# STM_mcu.net
KiCad netlist of a schematic drawn in Altium Designer
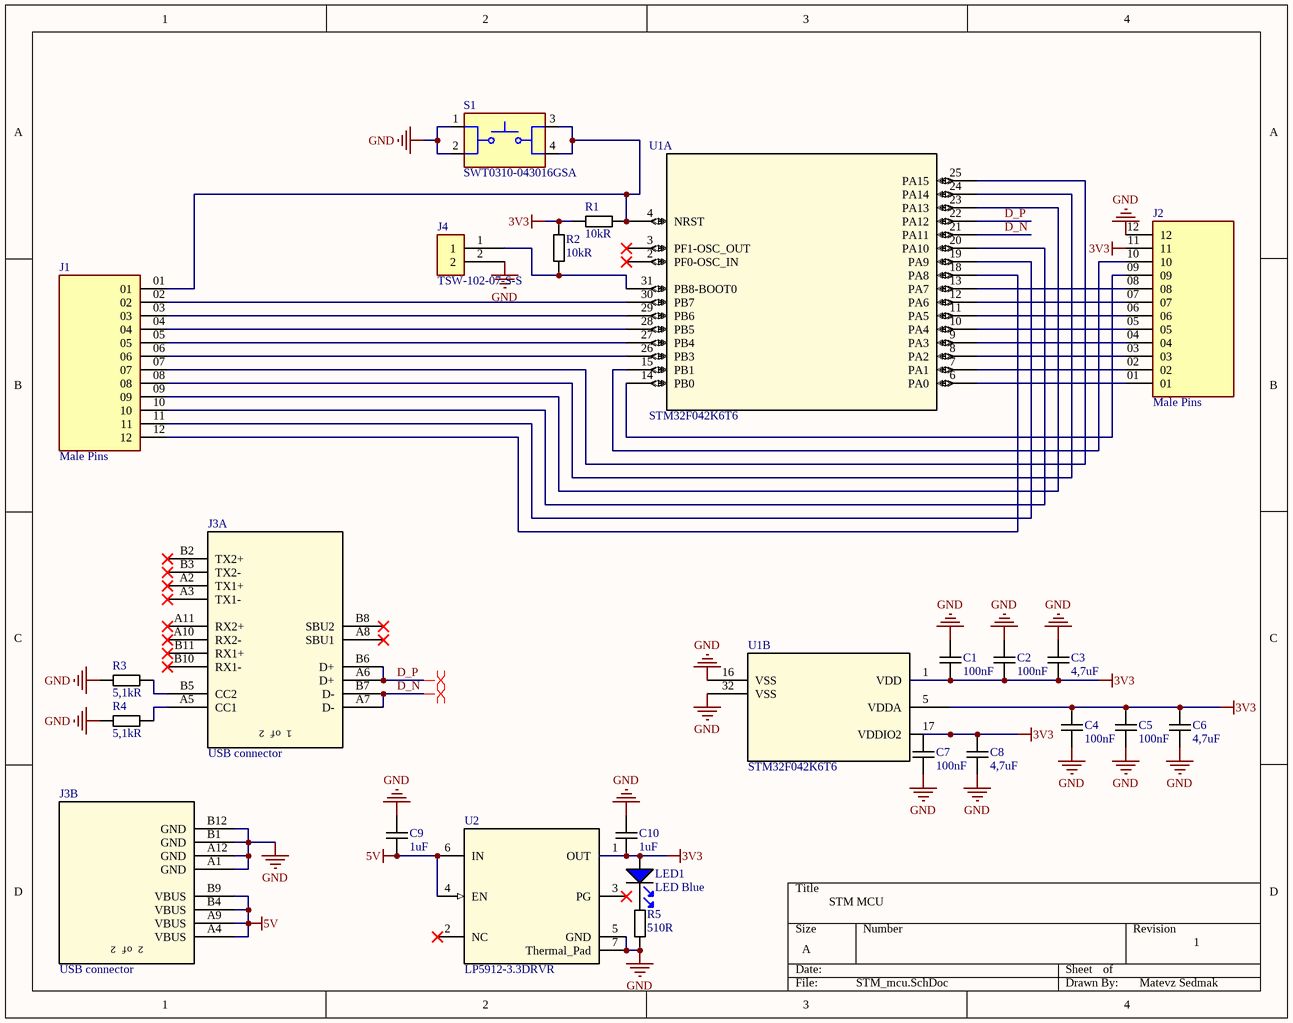
[diagram p0: STM_mcu.SchDoc]

(export (version "E")
  (design (tool "Eeschema 10.0.6"))
  (components
    (comp (ref "C1")
      (value "100nF")
      (footprint "CAPACITOR_0402")
      (description "0.1 µF ±20% 50V Ceramic Capacitor X5R 0402 (1005 Metric)")
      (fields (field (name "PART NUMBER") "CGA2B3X5R1H104M050BB"))
      (libsource (lib "STM_mcu") (part "100nF-50V-0402"))
    )
    (comp (ref "C2")
      (value "100nF")
      (footprint "CAPACITOR_0402")
      (description "0.1 µF ±20% 50V Ceramic Capacitor X5R 0402 (1005 Metric)")
      (fields (field (name "PART NUMBER") "CGA2B3X5R1H104M050BB"))
      (libsource (lib "STM_mcu") (part "100nF-50V-0402"))
    )
    (comp (ref "C3")
      (value "4,7uF")
      (footprint "CAPACITOR_0603")
      (description "4.7 µF ±10% 25V Ceramic Capacitor X5R 0603 (1608 Metric)")
      (fields (field (name "PART NUMBER") "C1608X5R1E475K080AC"))
      (libsource (lib "STM_mcu") (part "4,7uF-25V-0603"))
    )
    (comp (ref "C4")
      (value "100nF")
      (footprint "CAPACITOR_0402")
      (description "0.1 µF ±20% 50V Ceramic Capacitor X5R 0402 (1005 Metric)")
      (fields (field (name "PART NUMBER") "CGA2B3X5R1H104M050BB"))
      (libsource (lib "STM_mcu") (part "100nF-50V-0402"))
    )
    (comp (ref "C5")
      (value "100nF")
      (footprint "CAPACITOR_0402")
      (description "0.1 µF ±20% 50V Ceramic Capacitor X5R 0402 (1005 Metric)")
      (fields (field (name "PART NUMBER") "CGA2B3X5R1H104M050BB"))
      (libsource (lib "STM_mcu") (part "100nF-50V-0402"))
    )
    (comp (ref "C6")
      (value "4,7uF")
      (footprint "CAPACITOR_0603")
      (description "4.7 µF ±10% 25V Ceramic Capacitor X5R 0603 (1608 Metric)")
      (fields (field (name "PART NUMBER") "C1608X5R1E475K080AC"))
      (libsource (lib "STM_mcu") (part "4,7uF-25V-0603"))
    )
    (comp (ref "C7")
      (value "100nF")
      (footprint "CAPACITOR_0402")
      (description "0.1 µF ±20% 50V Ceramic Capacitor X5R 0402 (1005 Metric)")
      (fields (field (name "PART NUMBER") "CGA2B3X5R1H104M050BB"))
      (libsource (lib "STM_mcu") (part "100nF-50V-0402"))
    )
    (comp (ref "C8")
      (value "4,7uF")
      (footprint "CAPACITOR_0603")
      (description "4.7 µF ±10% 25V Ceramic Capacitor X5R 0603 (1608 Metric)")
      (fields (field (name "PART NUMBER") "C1608X5R1E475K080AC"))
      (libsource (lib "STM_mcu") (part "4,7uF-25V-0603"))
    )
    (comp (ref "C9")
      (value "1uF")
      (footprint "CAPACITOR_0603")
      (description "1 µF ±10% 25V Ceramic Capacitor X7R 0603 (1608 Metric)")
      (fields (field (name "PART NUMBER") "CGA3E1X7R1E105K080AC"))
      (libsource (lib "STM_mcu") (part "1uF-25V-0603"))
    )
    (comp (ref "C10")
      (value "1uF")
      (footprint "CAPACITOR_0603")
      (description "1 µF ±10% 25V Ceramic Capacitor X7R 0603 (1608 Metric)")
      (fields (field (name "PART NUMBER") "CGA3E1X7R1E105K080AC"))
      (libsource (lib "STM_mcu") (part "1uF-25V-0603"))
    )
    (comp (ref "J1")
      (value "Male Pins")
      (footprint "SAMTEC_TSW-112-07-L-S")
      (description "Connector Header Through Hole 12 position 0.100\" (2.54mm)")
      (fields (field (name "PART NUMBER") "TSW-112-07-L-S"))
      (libsource (lib "") (part "TSW-112-07-L-S_1"))
    )
    (comp (ref "J2")
      (value "Male Pins")
      (footprint "SAMTEC_TSW-112-07-L-S")
      (description "Connector Header Through Hole 12 position 0.100\" (2.54mm)")
      (fields (field (name "PART NUMBER") "TSW-112-07-L-S"))
      (libsource (lib "STM_mcu") (part "TSW-112-07-L-S"))
    )
    (comp (ref "J3")
      (value "USB connector")
      (footprint "USB_C_CONN_1054500101")
      (fields (field (name "PART NUMBER") "1054500101"))
      (libsource (lib "STM_mcu") (part "USB_1054500101"))
    )
    (comp (ref "J4")
      (value "TSW-102-07-S-S")
      (footprint "SAMTEC_TSW-102-07-L-S")
      (description "Connector Header Through Hole 2 position 0.100\" (2.54mm)")
      (libsource (lib "STM_mcu") (part "TSW-102-07-S-S"))
    )
    (comp (ref "LED1")
      (value "LED Blue")
      (footprint "LED_0603")
      (description "Blue 470nm LED Indication - Discrete 3.2V 0603 (1608 Metric)")
      (fields (field (name "PART NUMBER") "150060BS75000"))
      (libsource (lib "STM_mcu") (part "LED-Blue-0603"))
    )
    (comp (ref "R1")
      (value "10kR")
      (footprint "RESISTOR_0402")
      (description "10 kOhms ±1% 0.063W, 1/16W Chip Resistor 0402 (1005 Metric) Thick Film")
      (fields (field (name "PART NUMBER") "CRCW040210K0FKEDC"))
      (libsource (lib "STM_mcu") (part "10kR-1%-0402"))
    )
    (comp (ref "R2")
      (value "10kR")
      (footprint "RESISTOR_0402")
      (description "10 kOhms ±1% 0.063W, 1/16W Chip Resistor 0402 (1005 Metric) Thick Film")
      (fields (field (name "PART NUMBER") "CRCW040210K0FKEDC"))
      (libsource (lib "STM_mcu") (part "10kR-1%-0402"))
    )
    (comp (ref "R3")
      (value "5,1kR")
      (footprint "RESISTOR_0402")
      (description "5.1 kOhms ±1% 0.063W, 1/16W Chip Resistor 0402 (1005 Metric) Thick Film")
      (fields (field (name "PART NUMBER") "CRCW04025K10FKEDC"))
      (libsource (lib "STM_mcu") (part "5,1kR-1%-0402"))
    )
    (comp (ref "R4")
      (value "5,1kR")
      (footprint "RESISTOR_0402")
      (description "5.1 kOhms ±1% 0.063W, 1/16W Chip Resistor 0402 (1005 Metric) Thick Film")
      (fields (field (name "PART NUMBER") "CRCW04025K10FKEDC"))
      (libsource (lib "STM_mcu") (part "5,1kR-1%-0402"))
    )
    (comp (ref "R5")
      (value "510R")
      (footprint "RESISTOR_0402")
      (description "510 Ohms ±1% 0.063W, 1/16W Chip Resistor 0402 (1005 Metric) Automotive AEC-Q200 Thick Film")
      (fields (field (name "PART NUMBER") "CRCW0402510RFKED"))
      (libsource (lib "STM_mcu") (part "510R-1%-0402"))
    )
    (comp (ref "S1")
      (value "SWT0310-043016GSA")
      (footprint "SWT0310 - switch")
      (description "6mm x 6mm Gull Wing Tactile Switch")
      (libsource (lib "STM_mcu") (part "SWT0310-043016GSA"))
    )
    (comp (ref "U1")
      (value "STM32F042K6T6")
      (footprint "Quad32-STM32F042K6T6")
      (libsource (lib "STM_mcu") (part "STM32F042K6T6"))
    )
    (comp (ref "U2")
      (value "LP5912-3.3DRVR")
      (footprint "LP5912")
      (libsource (lib "STM_mcu") (part "LP5912-3.3DRVR"))
    )
  )
  (nets
    (net (code "1") (name "/D_N") (class "Default")
      (node (ref "J3") (pin "A7") (pinfunction "D-_A7") (pintype "passive"))
      (node (ref "J3") (pin "B7") (pinfunction "D-_B7") (pintype "passive"))
      (node (ref "U1") (pin "21") (pinfunction "PA11_21") (pintype "bidirectional"))
    )
    (net (code "2") (name "/D_P") (class "Default")
      (node (ref "J3") (pin "A6") (pinfunction "D+_A6") (pintype "passive"))
      (node (ref "J3") (pin "B6") (pinfunction "D+_B6") (pintype "passive"))
      (node (ref "U1") (pin "22") (pinfunction "PA12_22") (pintype "bidirectional"))
    )
    (net (code "3") (name "3V3") (class "Default")
      (node (ref "C1") (pin "1") (pinfunction "1_1") (pintype "passive"))
      (node (ref "C10") (pin "1") (pinfunction "1_1") (pintype "passive"))
      (node (ref "C2") (pin "1") (pinfunction "1_1") (pintype "passive"))
      (node (ref "C3") (pin "1") (pinfunction "1_1") (pintype "passive"))
      (node (ref "C4") (pin "1") (pinfunction "1_1") (pintype "passive"))
      (node (ref "C5") (pin "1") (pinfunction "1_1") (pintype "passive"))
      (node (ref "C6") (pin "1") (pinfunction "1_1") (pintype "passive"))
      (node (ref "C7") (pin "1") (pinfunction "1_1") (pintype "passive"))
      (node (ref "C8") (pin "1") (pinfunction "1_1") (pintype "passive"))
      (node (ref "J2") (pin "11") (pinfunction "11_11") (pintype "passive"))
      (node (ref "LED1") (pin "2") (pinfunction "A_2") (pintype "passive"))
      (node (ref "R1") (pin "1") (pinfunction "R1_1") (pintype "passive"))
      (node (ref "R2") (pin "1") (pinfunction "R1_1") (pintype "passive"))
      (node (ref "U1") (pin "1") (pinfunction "VDD_1") (pintype "power_in"))
      (node (ref "U1") (pin "17") (pinfunction "VDDIO2_17") (pintype "power_in"))
      (node (ref "U1") (pin "5") (pinfunction "VDDA_5") (pintype "power_in"))
      (node (ref "U2") (pin "1") (pinfunction "OUT_1") (pintype "power_in"))
    )
    (net (code "4") (name "5V") (class "Default")
      (node (ref "C9") (pin "1") (pinfunction "1_1") (pintype "passive"))
      (node (ref "J3") (pin "A4") (pinfunction "VBUS_A4") (pintype "power_in"))
      (node (ref "J3") (pin "A9") (pinfunction "VBUS_A9") (pintype "power_in"))
      (node (ref "J3") (pin "B4") (pinfunction "VBUS_B4") (pintype "power_in"))
      (node (ref "J3") (pin "B9") (pinfunction "VBUS_B9") (pintype "power_in"))
      (node (ref "U2") (pin "4") (pinfunction "EN_4") (pintype "input"))
      (node (ref "U2") (pin "6") (pinfunction "IN_6") (pintype "power_in"))
    )
    (net (code "5") (name "GND") (class "Default")
      (node (ref "C1") (pin "2") (pinfunction "2_2") (pintype "passive"))
      (node (ref "C10") (pin "2") (pinfunction "2_2") (pintype "passive"))
      (node (ref "C2") (pin "2") (pinfunction "2_2") (pintype "passive"))
      (node (ref "C3") (pin "2") (pinfunction "2_2") (pintype "passive"))
      (node (ref "C4") (pin "2") (pinfunction "2_2") (pintype "passive"))
      (node (ref "C5") (pin "2") (pinfunction "2_2") (pintype "passive"))
      (node (ref "C6") (pin "2") (pinfunction "2_2") (pintype "passive"))
      (node (ref "C7") (pin "2") (pinfunction "2_2") (pintype "passive"))
      (node (ref "C8") (pin "2") (pinfunction "2_2") (pintype "passive"))
      (node (ref "C9") (pin "2") (pinfunction "2_2") (pintype "passive"))
      (node (ref "J2") (pin "12") (pinfunction "12_12") (pintype "passive"))
      (node (ref "J3") (pin "A1") (pinfunction "GND_A1") (pintype "power_in"))
      (node (ref "J3") (pin "A12") (pinfunction "GND_A12") (pintype "power_in"))
      (node (ref "J3") (pin "B1") (pinfunction "GND_B1") (pintype "power_in"))
      (node (ref "J3") (pin "B12") (pinfunction "GND_B12") (pintype "power_in"))
      (node (ref "J4") (pin "2") (pinfunction "2_2") (pintype "passive"))
      (node (ref "R3") (pin "1") (pinfunction "R1_1") (pintype "passive"))
      (node (ref "R4") (pin "1") (pinfunction "R1_1") (pintype "passive"))
      (node (ref "R5") (pin "1") (pinfunction "R1_1") (pintype "passive"))
      (node (ref "S1") (pin "1") (pinfunction "1_1") (pintype "passive"))
      (node (ref "S1") (pin "2") (pinfunction "2_2") (pintype "passive"))
      (node (ref "U1") (pin "16") (pinfunction "VSS_16") (pintype "power_in"))
      (node (ref "U1") (pin "32") (pinfunction "VSS_32") (pintype "power_in"))
      (node (ref "U2") (pin "5") (pinfunction "GND_5") (pintype "power_in"))
      (node (ref "U2") (pin "7") (pinfunction "Thermal_Pad_7") (pintype "power_in"))
    )
    (net (code "6") (name "Net-(J3A-CC1)") (class "Default")
      (node (ref "J3") (pin "A5") (pinfunction "CC1_A5") (pintype "passive"))
      (node (ref "R4") (pin "2") (pinfunction "R2_2") (pintype "passive"))
    )
    (net (code "7") (name "Net-(J3A-CC2)") (class "Default")
      (node (ref "J3") (pin "B5") (pinfunction "CC2_B5") (pintype "passive"))
      (node (ref "R3") (pin "2") (pinfunction "R2_2") (pintype "passive"))
    )
    (net (code "8") (name "Net-(LED1-C)") (class "Default")
      (node (ref "LED1") (pin "1") (pinfunction "C_1") (pintype "passive"))
      (node (ref "R5") (pin "2") (pinfunction "R2_2") (pintype "passive"))
    )
    (net (code "9") (name "Net-(R1-R2)") (class "Default")
      (node (ref "J1") (pin "01") (pinfunction "01_01") (pintype "passive"))
      (node (ref "R1") (pin "2") (pinfunction "R2_2") (pintype "passive"))
      (node (ref "S1") (pin "3") (pinfunction "3_3") (pintype "passive"))
      (node (ref "S1") (pin "4") (pinfunction "4_4") (pintype "passive"))
      (node (ref "U1") (pin "4") (pinfunction "NRST_4") (pintype "bidirectional"))
    )
    (net (code "10") (name "Net-(R2-R2)") (class "Default")
      (node (ref "J4") (pin "1") (pinfunction "1_1") (pintype "passive"))
      (node (ref "R2") (pin "2") (pinfunction "R2_2") (pintype "passive"))
      (node (ref "U1") (pin "31") (pinfunction "PB8-BOOT0_31") (pintype "bidirectional"))
    )
    (net (code "11") (name "Net-(U1A-PA0)") (class "Default")
      (node (ref "J2") (pin "01") (pinfunction "01_01") (pintype "passive"))
      (node (ref "U1") (pin "6") (pinfunction "PA0_6") (pintype "bidirectional"))
    )
    (net (code "12") (name "Net-(U1A-PA1)") (class "Default")
      (node (ref "J2") (pin "02") (pinfunction "02_02") (pintype "passive"))
      (node (ref "U1") (pin "7") (pinfunction "PA1_7") (pintype "bidirectional"))
    )
    (net (code "13") (name "Net-(U1A-PA2)") (class "Default")
      (node (ref "J2") (pin "03") (pinfunction "03_03") (pintype "passive"))
      (node (ref "U1") (pin "8") (pinfunction "PA2_8") (pintype "bidirectional"))
    )
    (net (code "14") (name "Net-(U1A-PA3)") (class "Default")
      (node (ref "J2") (pin "04") (pinfunction "04_04") (pintype "passive"))
      (node (ref "U1") (pin "9") (pinfunction "PA3_9") (pintype "bidirectional"))
    )
    (net (code "15") (name "Net-(U1A-PA4)") (class "Default")
      (node (ref "J2") (pin "05") (pinfunction "05_05") (pintype "passive"))
      (node (ref "U1") (pin "10") (pinfunction "PA4_10") (pintype "bidirectional"))
    )
    (net (code "16") (name "Net-(U1A-PA5)") (class "Default")
      (node (ref "J2") (pin "06") (pinfunction "06_06") (pintype "passive"))
      (node (ref "U1") (pin "11") (pinfunction "PA5_11") (pintype "bidirectional"))
    )
    (net (code "17") (name "Net-(U1A-PA6)") (class "Default")
      (node (ref "J2") (pin "07") (pinfunction "07_07") (pintype "passive"))
      (node (ref "U1") (pin "12") (pinfunction "PA6_12") (pintype "bidirectional"))
    )
    (net (code "18") (name "Net-(U1A-PA7)") (class "Default")
      (node (ref "J2") (pin "08") (pinfunction "08_08") (pintype "passive"))
      (node (ref "U1") (pin "13") (pinfunction "PA7_13") (pintype "bidirectional"))
    )
    (net (code "19") (name "Net-(U1A-PA8)") (class "Default")
      (node (ref "J1") (pin "12") (pinfunction "12_12") (pintype "passive"))
      (node (ref "U1") (pin "18") (pinfunction "PA8_18") (pintype "bidirectional"))
    )
    (net (code "20") (name "Net-(U1A-PA9)") (class "Default")
      (node (ref "J1") (pin "11") (pinfunction "11_11") (pintype "passive"))
      (node (ref "U1") (pin "19") (pinfunction "PA9_19") (pintype "bidirectional"))
    )
    (net (code "21") (name "Net-(U1A-PA10)") (class "Default")
      (node (ref "J1") (pin "10") (pinfunction "10_10") (pintype "passive"))
      (node (ref "U1") (pin "20") (pinfunction "PA10_20") (pintype "bidirectional"))
    )
    (net (code "22") (name "Net-(U1A-PA13)") (class "Default")
      (node (ref "J1") (pin "09") (pinfunction "09_09") (pintype "passive"))
      (node (ref "U1") (pin "23") (pinfunction "PA13_23") (pintype "bidirectional"))
    )
    (net (code "23") (name "Net-(U1A-PA14)") (class "Default")
      (node (ref "J1") (pin "08") (pinfunction "08_08") (pintype "passive"))
      (node (ref "U1") (pin "24") (pinfunction "PA14_24") (pintype "bidirectional"))
    )
    (net (code "24") (name "Net-(U1A-PA15)") (class "Default")
      (node (ref "J1") (pin "07") (pinfunction "07_07") (pintype "passive"))
      (node (ref "U1") (pin "25") (pinfunction "PA15_25") (pintype "bidirectional"))
    )
    (net (code "25") (name "Net-(U1A-PB0)") (class "Default")
      (node (ref "J2") (pin "09") (pinfunction "09_09") (pintype "passive"))
      (node (ref "U1") (pin "14") (pinfunction "PB0_14") (pintype "bidirectional"))
    )
    (net (code "26") (name "Net-(U1A-PB1)") (class "Default")
      (node (ref "J2") (pin "10") (pinfunction "10_10") (pintype "passive"))
      (node (ref "U1") (pin "15") (pinfunction "PB1_15") (pintype "bidirectional"))
    )
    (net (code "27") (name "Net-(U1A-PB3)") (class "Default")
      (node (ref "J1") (pin "06") (pinfunction "06_06") (pintype "passive"))
      (node (ref "U1") (pin "26") (pinfunction "PB3_26") (pintype "bidirectional"))
    )
    (net (code "28") (name "Net-(U1A-PB4)") (class "Default")
      (node (ref "J1") (pin "05") (pinfunction "05_05") (pintype "passive"))
      (node (ref "U1") (pin "27") (pinfunction "PB4_27") (pintype "bidirectional"))
    )
    (net (code "29") (name "Net-(U1A-PB5)") (class "Default")
      (node (ref "J1") (pin "04") (pinfunction "04_04") (pintype "passive"))
      (node (ref "U1") (pin "28") (pinfunction "PB5_28") (pintype "bidirectional"))
    )
    (net (code "30") (name "Net-(U1A-PB6)") (class "Default")
      (node (ref "J1") (pin "03") (pinfunction "03_03") (pintype "passive"))
      (node (ref "U1") (pin "29") (pinfunction "PB6_29") (pintype "bidirectional"))
    )
    (net (code "31") (name "Net-(U1A-PB7)") (class "Default")
      (node (ref "J1") (pin "02") (pinfunction "02_02") (pintype "passive"))
      (node (ref "U1") (pin "30") (pinfunction "PB7_30") (pintype "bidirectional"))
    )
    (net (code "32") (name "unconnected-(J3A-RX1+-PadB11)") (class "Default")
      (node (ref "J3") (pin "B11") (pinfunction "RX1+_B11") (pintype "passive+no_connect"))
    )
    (net (code "33") (name "unconnected-(J3A-RX1--PadB10)") (class "Default")
      (node (ref "J3") (pin "B10") (pinfunction "RX1-_B10") (pintype "passive+no_connect"))
    )
    (net (code "34") (name "unconnected-(J3A-RX2+-PadA11)") (class "Default")
      (node (ref "J3") (pin "A11") (pinfunction "RX2+_A11") (pintype "passive+no_connect"))
    )
    (net (code "35") (name "unconnected-(J3A-RX2--PadA10)") (class "Default")
      (node (ref "J3") (pin "A10") (pinfunction "RX2-_A10") (pintype "passive+no_connect"))
    )
    (net (code "36") (name "unconnected-(J3A-SBU1-PadA8)") (class "Default")
      (node (ref "J3") (pin "A8") (pinfunction "SBU1_A8") (pintype "passive+no_connect"))
    )
    (net (code "37") (name "unconnected-(J3A-SBU2-PadB8)") (class "Default")
      (node (ref "J3") (pin "B8") (pinfunction "SBU2_B8") (pintype "passive+no_connect"))
    )
    (net (code "38") (name "unconnected-(J3A-TX1+-PadA2)") (class "Default")
      (node (ref "J3") (pin "A2") (pinfunction "TX1+_A2") (pintype "passive+no_connect"))
    )
    (net (code "39") (name "unconnected-(J3A-TX1--PadA3)") (class "Default")
      (node (ref "J3") (pin "A3") (pinfunction "TX1-_A3") (pintype "passive+no_connect"))
    )
    (net (code "40") (name "unconnected-(J3A-TX2+-PadB2)") (class "Default")
      (node (ref "J3") (pin "B2") (pinfunction "TX2+_B2") (pintype "passive+no_connect"))
    )
    (net (code "41") (name "unconnected-(J3A-TX2--PadB3)") (class "Default")
      (node (ref "J3") (pin "B3") (pinfunction "TX2-_B3") (pintype "passive+no_connect"))
    )
    (net (code "42") (name "unconnected-(U1A-PF0-OSC_IN-Pad2)") (class "Default")
      (node (ref "U1") (pin "2") (pinfunction "PF0-OSC_IN_2") (pintype "bidirectional+no_connect"))
    )
    (net (code "43") (name "unconnected-(U1A-PF1-OSC_OUT-Pad3)") (class "Default")
      (node (ref "U1") (pin "3") (pinfunction "PF1-OSC_OUT_3") (pintype "bidirectional+no_connect"))
    )
    (net (code "44") (name "unconnected-(U2-NC-Pad2)") (class "Default")
      (node (ref "U2") (pin "2") (pinfunction "NC_2") (pintype "passive+no_connect"))
    )
    (net (code "45") (name "unconnected-(U2-PG-Pad3)") (class "Default")
      (node (ref "U2") (pin "3") (pinfunction "PG_3") (pintype "open_collector+no_connect"))
    )
  )
)
